# LCD_board.net
KiCad netlist of a schematic drawn in EAGLE
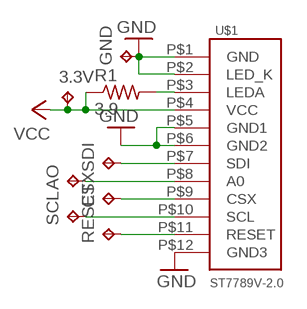
[diagram p0: schematic, sheet 1]

(export (version "E")
  (design (tool "Eeschema 10.0.6"))
  (components
    (comp (ref "3.3V")
      (value "TPTP18RECT")
      (footprint "eagle-import:TP18RECT")
      (libsource (lib "eagle-import") (part "TPTP18RECT"))
    )
    (comp (ref "AO")
      (value "TPTP18RECT")
      (footprint "eagle-import:TP18RECT")
      (libsource (lib "eagle-import") (part "TPTP18RECT"))
    )
    (comp (ref "CSX")
      (value "TPTP18RECT")
      (footprint "eagle-import:TP18RECT")
      (libsource (lib "eagle-import") (part "TPTP18RECT"))
    )
    (comp (ref "GND")
      (value "TPTP18RECT")
      (footprint "eagle-import:TP18RECT")
      (libsource (lib "eagle-import") (part "TPTP18RECT"))
    )
    (comp (ref "R1")
      (value "3.9")
      (footprint "eagle-import:R0603")
      (libsource (lib "eagle-import") (part "R-US_R0603"))
    )
    (comp (ref "RESET")
      (value "TPTP18RECT")
      (footprint "eagle-import:TP18RECT")
      (libsource (lib "eagle-import") (part "TPTP18RECT"))
    )
    (comp (ref "SCL")
      (value "TPTP18RECT")
      (footprint "eagle-import:TP18RECT")
      (libsource (lib "eagle-import") (part "TPTP18RECT"))
    )
    (comp (ref "SDI")
      (value "TPTP18RECT")
      (footprint "eagle-import:TP18RECT")
      (libsource (lib "eagle-import") (part "TPTP18RECT"))
    )
    (comp (ref "U$1")
      (value "ST7789V-2.0")
      (footprint "eagle-import:ST7789V-2.0")
      (libsource (lib "eagle-import") (part "ST7789V-2.0"))
    )
  )
  (nets
    (net (code "1") (name "GND") (class "Default")
      (node (ref "GND") (pin "TP") (pinfunction "TP_TP") (pintype "input"))
      (node (ref "U$1") (pin "P$1") (pinfunction "GND_P$1") (pintype "bidirectional"))
      (node (ref "U$1") (pin "P$12") (pinfunction "GND3_P$12") (pintype "bidirectional"))
      (node (ref "U$1") (pin "P$2") (pinfunction "LED_K_P$2") (pintype "bidirectional"))
      (node (ref "U$1") (pin "P$5") (pinfunction "GND1_P$5") (pintype "bidirectional"))
      (node (ref "U$1") (pin "P$6") (pinfunction "GND2_P$6") (pintype "bidirectional"))
    )
    (net (code "2") (name "Net-(U$1-A0)") (class "Default")
      (node (ref "AO") (pin "TP") (pinfunction "TP_TP") (pintype "input"))
      (node (ref "U$1") (pin "P$8") (pinfunction "A0_P$8") (pintype "bidirectional"))
    )
    (net (code "3") (name "Net-(U$1-CSX)") (class "Default")
      (node (ref "CSX") (pin "TP") (pinfunction "TP_TP") (pintype "input"))
      (node (ref "U$1") (pin "P$9") (pinfunction "CSX_P$9") (pintype "bidirectional"))
    )
    (net (code "4") (name "Net-(U$1-LEDA)") (class "Default")
      (node (ref "R1") (pin "2") (pinfunction "2_2") (pintype "passive"))
      (node (ref "U$1") (pin "P$3") (pinfunction "LEDA_P$3") (pintype "bidirectional"))
    )
    (net (code "5") (name "Net-(U$1-RESET)") (class "Default")
      (node (ref "RESET") (pin "TP") (pinfunction "TP_TP") (pintype "input"))
      (node (ref "U$1") (pin "P$11") (pinfunction "RESET_P$11") (pintype "bidirectional"))
    )
    (net (code "6") (name "Net-(U$1-SCL)") (class "Default")
      (node (ref "SCL") (pin "TP") (pinfunction "TP_TP") (pintype "input"))
      (node (ref "U$1") (pin "P$10") (pinfunction "SCL_P$10") (pintype "bidirectional"))
    )
    (net (code "7") (name "Net-(U$1-SDI)") (class "Default")
      (node (ref "SDI") (pin "TP") (pinfunction "TP_TP") (pintype "input"))
      (node (ref "U$1") (pin "P$7") (pinfunction "SDI_P$7") (pintype "bidirectional"))
    )
    (net (code "8") (name "VCC") (class "Default")
      (node (ref "3.3V") (pin "TP") (pinfunction "TP_TP") (pintype "input"))
      (node (ref "R1") (pin "1") (pinfunction "1_1") (pintype "passive"))
      (node (ref "U$1") (pin "P$4") (pinfunction "VCC_P$4") (pintype "bidirectional"))
    )
  )
)
